# function_generator.net
KiCad netlist of a schematic drawn in EAGLE
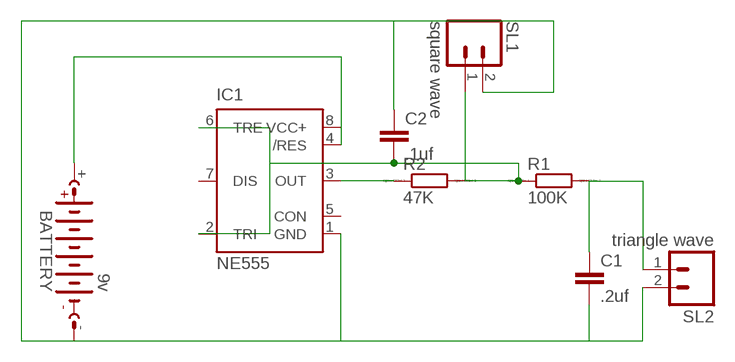
[diagram p0: schematic, sheet 1]

(export (version "E")
  (design (tool "Eeschema 10.0.6"))
  (components
    (comp (ref "BATTERY")
      (value "9v")
      (footprint "eagle-import:AB9V")
      (libsource (lib "eagle-import") (part "AB9V"))
    )
    (comp (ref "C1")
      (value ".2uf")
      (footprint "eagle-import:C2.5-3")
      (libsource (lib "eagle-import") (part "C2,5-3"))
    )
    (comp (ref "C2")
      (value ".1uf")
      (footprint "eagle-import:C2.5-3")
      (libsource (lib "eagle-import") (part "C2,5-3"))
    )
    (comp (ref "IC1")
      (value "NE555")
      (footprint "eagle-import:DIL-08")
      (fields (field (name "MF") "Arrow Electronics") (field (name "MPN") "NE555N"))
      (libsource (lib "eagle-import") (part "NE555"))
    )
    (comp (ref "R1")
      (value "100K")
      (footprint "eagle-import:0204_7")
      (libsource (lib "eagle-import") (part "R0204/7"))
    )
    (comp (ref "R2")
      (value "47K")
      (footprint "eagle-import:0204_7")
      (libsource (lib "eagle-import") (part "R0204/7"))
    )
    (comp (ref "SL1")
      (value "square wave")
      (footprint "eagle-import:02P")
      (libsource (lib "eagle-import") (part "M02"))
    )
    (comp (ref "SL2")
      (value "triangle wave")
      (footprint "eagle-import:02P")
      (libsource (lib "eagle-import") (part "M02"))
    )
  )
  (nets
    (net (code "1") (name "Net-(C1-Pad1)") (class "Default")
      (node (ref "C1") (pin "1") (pinfunction "1_1") (pintype "passive"))
      (node (ref "R1") (pin "2") (pinfunction "2_2") (pintype "passive"))
      (node (ref "SL2") (pin "1") (pinfunction "1_1") (pintype "passive"))
    )
    (net (code "2") (name "Net-(IC1-GND)") (class "Default")
      (node (ref "BATTERY") (pin "-") (pinfunction "-_-") (pintype "passive"))
      (node (ref "C1") (pin "2") (pinfunction "2_2") (pintype "passive"))
      (node (ref "C2") (pin "1") (pinfunction "1_1") (pintype "passive"))
      (node (ref "IC1") (pin "1") (pinfunction "GND_1") (pintype "power_in"))
      (node (ref "SL1") (pin "2") (pinfunction "2_2") (pintype "passive"))
      (node (ref "SL2") (pin "2") (pinfunction "2_2") (pintype "passive"))
    )
    (net (code "3") (name "Net-(IC1-OUT)") (class "Default")
      (node (ref "IC1") (pin "3") (pinfunction "OUT_3") (pintype "output"))
      (node (ref "R2") (pin "1") (pinfunction "1_1") (pintype "passive"))
    )
    (net (code "4") (name "Net-(IC1-TRE)") (class "Default")
      (node (ref "C2") (pin "2") (pinfunction "2_2") (pintype "passive"))
      (node (ref "IC1") (pin "2") (pinfunction "TRI_2") (pintype "input"))
      (node (ref "IC1") (pin "6") (pinfunction "TRE_6") (pintype "input"))
      (node (ref "R1") (pin "1") (pinfunction "1_1") (pintype "passive"))
      (node (ref "R2") (pin "2") (pinfunction "2_2") (pintype "passive"))
      (node (ref "SL1") (pin "1") (pinfunction "1_1") (pintype "passive"))
    )
    (net (code "5") (name "Net-(IC1-VCC+)") (class "Default")
      (node (ref "BATTERY") (pin "+") (pinfunction "+_+") (pintype "passive"))
      (node (ref "IC1") (pin "4") (pinfunction "/RES_4") (pintype "input"))
      (node (ref "IC1") (pin "8") (pinfunction "VCC+_8") (pintype "power_in"))
    )
    (net (code "6") (name "unconnected-(IC1-CON-Pad5)") (class "Default")
      (node (ref "IC1") (pin "5") (pinfunction "CON_5") (pintype "input"))
    )
    (net (code "7") (name "unconnected-(IC1-DIS-Pad7)") (class "Default")
      (node (ref "IC1") (pin "7") (pinfunction "DIS_7") (pintype "input"))
    )
  )
)
